# crow.net
KiCad netlist of a schematic drawn in EAGLE
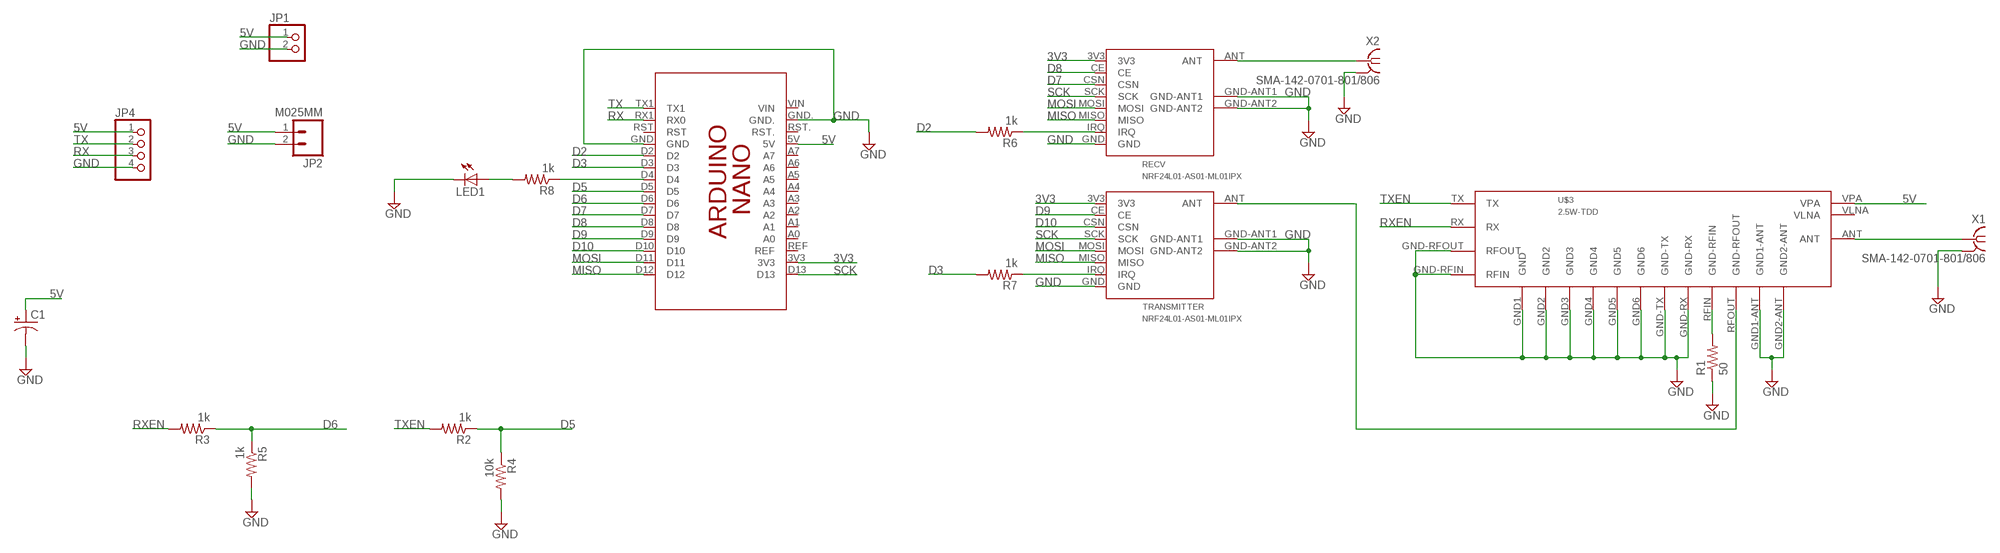
[diagram p0: schematic, sheet 1]

(export (version "E")
  (design (tool "Eeschema 10.0.6"))
  (components
    (comp (ref "C1")
      (value "CPOL-USUD-5X5,8")
      (footprint "eagle-import:UD-5X5,8_NICHICON")
      (libsource (lib "eagle-import") (part "CPOL-USUD-5X5,8"))
    )
    (comp (ref "JP1")
      (value "PINHD-1X2")
      (footprint "eagle-import:1X02")
      (libsource (lib "eagle-import") (part "PINHD-1X2"))
    )
    (comp (ref "JP2")
      (value "M025MM")
      (footprint "eagle-import:SCREWTERMINAL-5MM-2")
      (libsource (lib "eagle-import") (part "M025MM"))
    )
    (comp (ref "JP4")
      (value "PINHD-1X4")
      (footprint "eagle-import:1X04")
      (libsource (lib "eagle-import") (part "PINHD-1X4"))
    )
    (comp (ref "LED1")
      (value "LEDSML0805")
      (footprint "eagle-import:SML0805")
      (libsource (lib "eagle-import") (part "LEDSML0805"))
    )
    (comp (ref "PCB1")
      (value "ARDUINO_NANO_EXT")
      (footprint "eagle-import:ARDUINO_NANO")
      (libsource (lib "eagle-import") (part "ARDUINO_NANO_EXT"))
    )
    (comp (ref "R1")
      (value "50")
      (footprint "eagle-import:M0805")
      (libsource (lib "eagle-import") (part "R-US_M0805"))
    )
    (comp (ref "R2")
      (value "1k")
      (footprint "eagle-import:M0805")
      (libsource (lib "eagle-import") (part "R-US_M0805"))
    )
    (comp (ref "R3")
      (value "1k")
      (footprint "eagle-import:M0805")
      (libsource (lib "eagle-import") (part "R-US_M0805"))
    )
    (comp (ref "R4")
      (value "10k")
      (footprint "eagle-import:M0805")
      (libsource (lib "eagle-import") (part "R-US_M0805"))
    )
    (comp (ref "R5")
      (value "1k")
      (footprint "eagle-import:M0805")
      (libsource (lib "eagle-import") (part "R-US_M0805"))
    )
    (comp (ref "R6")
      (value "1k")
      (footprint "eagle-import:M0805")
      (libsource (lib "eagle-import") (part "R-US_M0805"))
    )
    (comp (ref "R7")
      (value "1k")
      (footprint "eagle-import:M0805")
      (libsource (lib "eagle-import") (part "R-US_M0805"))
    )
    (comp (ref "R8")
      (value "1k")
      (footprint "eagle-import:M0805")
      (libsource (lib "eagle-import") (part "R-US_M0805"))
    )
    (comp (ref "RECV")
      (value "NRF24L01-AS01-ML01IPX")
      (footprint "eagle-import:AS01-ML01IPX")
      (libsource (lib "eagle-import") (part "NRF24L01-AS01-ML01IPX"))
    )
    (comp (ref "TRANSMITTER")
      (value "NRF24L01-AS01-ML01IPX")
      (footprint "eagle-import:AS01-ML01IPX")
      (libsource (lib "eagle-import") (part "NRF24L01-AS01-ML01IPX"))
    )
    (comp (ref "U$3")
      (value "2.5W-TDD")
      (footprint "eagle-import:2.5W-TDD")
      (libsource (lib "eagle-import") (part "2.5W-TDD"))
    )
    (comp (ref "X1")
      (value "SMA-142-0701-801/806")
      (footprint "eagle-import:J502-ND-142-0701-801_806")
      (fields (field (name "MF") "JOHNSON COMPONENTS") (field (name "MPN") "142-0701-801"))
      (libsource (lib "eagle-import") (part "SMA-142-0701-801/806"))
    )
    (comp (ref "X2")
      (value "SMA-142-0701-801/806")
      (footprint "eagle-import:J502-ND-142-0701-801_806")
      (fields (field (name "MF") "JOHNSON COMPONENTS") (field (name "MPN") "142-0701-801"))
      (libsource (lib "eagle-import") (part "SMA-142-0701-801/806"))
    )
  )
  (nets
    (net (code "1") (name "/3V3") (class "Default")
      (node (ref "PCB1") (pin "3V3") (pinfunction "3V3_3V3") (pintype "bidirectional"))
      (node (ref "RECV") (pin "3V3") (pinfunction "3V3_3V3") (pintype "power_in"))
      (node (ref "TRANSMITTER") (pin "3V3") (pinfunction "3V3_3V3") (pintype "power_in"))
    )
    (net (code "2") (name "/5V") (class "Default")
      (node (ref "C1") (pin "+") (pinfunction "+_+") (pintype "passive"))
      (node (ref "JP1") (pin "1") (pinfunction "1_1") (pintype "passive"))
      (node (ref "JP2") (pin "1") (pinfunction "1_1") (pintype "passive"))
      (node (ref "JP4") (pin "1") (pinfunction "1_1") (pintype "passive"))
      (node (ref "PCB1") (pin "5V") (pinfunction "5V_5V") (pintype "bidirectional"))
      (node (ref "U$3") (pin "VPA") (pinfunction "VPA_VPA") (pintype "power_in"))
    )
    (net (code "3") (name "/D2") (class "Default")
      (node (ref "PCB1") (pin "D2") (pinfunction "D2_D2") (pintype "bidirectional"))
      (node (ref "R6") (pin "2") (pinfunction "2_2") (pintype "passive"))
    )
    (net (code "4") (name "/D3") (class "Default")
      (node (ref "PCB1") (pin "D3") (pinfunction "D3_D3") (pintype "bidirectional"))
      (node (ref "R7") (pin "2") (pinfunction "2_2") (pintype "passive"))
    )
    (net (code "5") (name "/D5") (class "Default")
      (node (ref "PCB1") (pin "D5") (pinfunction "D5_D5") (pintype "bidirectional"))
      (node (ref "R2") (pin "1") (pinfunction "1_1") (pintype "passive"))
      (node (ref "R4") (pin "1") (pinfunction "1_1") (pintype "passive"))
    )
    (net (code "6") (name "/D6") (class "Default")
      (node (ref "PCB1") (pin "D6") (pinfunction "D6_D6") (pintype "bidirectional"))
      (node (ref "R3") (pin "1") (pinfunction "1_1") (pintype "passive"))
      (node (ref "R5") (pin "1") (pinfunction "1_1") (pintype "passive"))
    )
    (net (code "7") (name "/D7") (class "Default")
      (node (ref "PCB1") (pin "D7") (pinfunction "D7_D7") (pintype "bidirectional"))
      (node (ref "RECV") (pin "CSN") (pinfunction "CSN_CSN") (pintype "input"))
    )
    (net (code "8") (name "/D8") (class "Default")
      (node (ref "PCB1") (pin "D8") (pinfunction "D8_D8") (pintype "bidirectional"))
      (node (ref "RECV") (pin "CE") (pinfunction "CE_CE") (pintype "input"))
    )
    (net (code "9") (name "/D9") (class "Default")
      (node (ref "PCB1") (pin "D9") (pinfunction "D9_D9") (pintype "bidirectional"))
      (node (ref "TRANSMITTER") (pin "CE") (pinfunction "CE_CE") (pintype "input"))
    )
    (net (code "10") (name "/D10") (class "Default")
      (node (ref "PCB1") (pin "D10") (pinfunction "D10_D10") (pintype "bidirectional"))
      (node (ref "TRANSMITTER") (pin "CSN") (pinfunction "CSN_CSN") (pintype "input"))
    )
    (net (code "11") (name "/MISO") (class "Default")
      (node (ref "PCB1") (pin "D12") (pinfunction "D12_D12") (pintype "bidirectional"))
      (node (ref "RECV") (pin "MISO") (pinfunction "MISO_MISO") (pintype "output"))
      (node (ref "TRANSMITTER") (pin "MISO") (pinfunction "MISO_MISO") (pintype "output"))
    )
    (net (code "12") (name "/MOSI") (class "Default")
      (node (ref "PCB1") (pin "D11") (pinfunction "D11_D11") (pintype "bidirectional"))
      (node (ref "RECV") (pin "MOSI") (pinfunction "MOSI_MOSI") (pintype "input"))
      (node (ref "TRANSMITTER") (pin "MOSI") (pinfunction "MOSI_MOSI") (pintype "input"))
    )
    (net (code "13") (name "/RX") (class "Default")
      (node (ref "JP4") (pin "3") (pinfunction "3_3") (pintype "passive"))
      (node (ref "PCB1") (pin "RX1") (pinfunction "RX0_RX1") (pintype "bidirectional"))
    )
    (net (code "14") (name "/RXEN") (class "Default")
      (node (ref "R3") (pin "2") (pinfunction "2_2") (pintype "passive"))
      (node (ref "U$3") (pin "RX") (pinfunction "RX_RX") (pintype "bidirectional"))
    )
    (net (code "15") (name "/SCK") (class "Default")
      (node (ref "PCB1") (pin "D13") (pinfunction "D13_D13") (pintype "bidirectional"))
      (node (ref "RECV") (pin "SCK") (pinfunction "SCK_SCK") (pintype "input"))
      (node (ref "TRANSMITTER") (pin "SCK") (pinfunction "SCK_SCK") (pintype "input"))
    )
    (net (code "16") (name "/TX") (class "Default")
      (node (ref "JP4") (pin "2") (pinfunction "2_2") (pintype "passive"))
      (node (ref "PCB1") (pin "TX1") (pinfunction "TX1_TX1") (pintype "bidirectional"))
    )
    (net (code "17") (name "/TXEN") (class "Default")
      (node (ref "R2") (pin "2") (pinfunction "2_2") (pintype "passive"))
      (node (ref "U$3") (pin "TX") (pinfunction "TX_TX") (pintype "bidirectional"))
    )
    (net (code "18") (name "/VLNA") (class "Default")
      (node (ref "U$3") (pin "VLNA") (pinfunction "VLNA_VLNA") (pintype "power_in"))
    )
    (net (code "19") (name "GND") (class "Default")
      (node (ref "C1") (pin "-") (pinfunction "-_-") (pintype "passive"))
      (node (ref "JP1") (pin "2") (pinfunction "2_2") (pintype "passive"))
      (node (ref "JP2") (pin "2") (pinfunction "2_2") (pintype "passive"))
      (node (ref "JP4") (pin "4") (pinfunction "4_4") (pintype "passive"))
      (node (ref "LED1") (pin "C") (pinfunction "C_C") (pintype "passive"))
      (node (ref "PCB1") (pin "GND") (pinfunction "GND_GND") (pintype "bidirectional"))
      (node (ref "PCB1") (pin "GND.") (pinfunction "GND._GND.") (pintype "bidirectional"))
      (node (ref "R1") (pin "1") (pinfunction "1_1") (pintype "passive"))
      (node (ref "R4") (pin "2") (pinfunction "2_2") (pintype "passive"))
      (node (ref "R5") (pin "2") (pinfunction "2_2") (pintype "passive"))
      (node (ref "RECV") (pin "GND") (pinfunction "GND_GND") (pintype "power_in"))
      (node (ref "RECV") (pin "GND-ANT1") (pinfunction "GND-ANT1_GND-ANT1") (pintype "power_in"))
      (node (ref "RECV") (pin "GND-ANT2") (pinfunction "GND-ANT2_GND-ANT2") (pintype "power_in"))
      (node (ref "TRANSMITTER") (pin "GND") (pinfunction "GND_GND") (pintype "power_in"))
      (node (ref "TRANSMITTER") (pin "GND-ANT1") (pinfunction "GND-ANT1_GND-ANT1") (pintype "power_in"))
      (node (ref "TRANSMITTER") (pin "GND-ANT2") (pinfunction "GND-ANT2_GND-ANT2") (pintype "power_in"))
      (node (ref "U$3") (pin "GND-RFIN") (pinfunction "RFIN_GND-RFIN") (pintype "output"))
      (node (ref "U$3") (pin "GND-RFOUT") (pinfunction "RFOUT_GND-RFOUT") (pintype "input"))
      (node (ref "U$3") (pin "GND-RX") (pinfunction "GND-RX_GND-RX") (pintype "power_in"))
      (node (ref "U$3") (pin "GND-TX") (pinfunction "GND-TX_GND-TX") (pintype "power_in"))
      (node (ref "U$3") (pin "GND1") (pinfunction "GND_GND1") (pintype "power_in"))
      (node (ref "U$3") (pin "GND1-ANT") (pinfunction "GND1-ANT_GND1-ANT") (pintype "power_in"))
      (node (ref "U$3") (pin "GND2") (pinfunction "GND2_GND2") (pintype "power_in"))
      (node (ref "U$3") (pin "GND2-ANT") (pinfunction "GND2-ANT_GND2-ANT") (pintype "power_in"))
      (node (ref "U$3") (pin "GND3") (pinfunction "GND3_GND3") (pintype "power_in"))
      (node (ref "U$3") (pin "GND4") (pinfunction "GND4_GND4") (pintype "power_in"))
      (node (ref "U$3") (pin "GND5") (pinfunction "GND5_GND5") (pintype "power_in"))
      (node (ref "U$3") (pin "GND6") (pinfunction "GND6_GND6") (pintype "power_in"))
      (node (ref "X1") (pin "G@1") (pinfunction "2_G@1") (pintype "passive"))
      (node (ref "X1") (pin "G@2") (pinfunction "2_G@2") (pintype "passive"))
      (node (ref "X1") (pin "G@3") (pinfunction "2_G@3") (pintype "passive"))
      (node (ref "X1") (pin "G@4") (pinfunction "2_G@4") (pintype "passive"))
      (node (ref "X2") (pin "G@1") (pinfunction "2_G@1") (pintype "passive"))
      (node (ref "X2") (pin "G@2") (pinfunction "2_G@2") (pintype "passive"))
      (node (ref "X2") (pin "G@3") (pinfunction "2_G@3") (pintype "passive"))
      (node (ref "X2") (pin "G@4") (pinfunction "2_G@4") (pintype "passive"))
    )
    (net (code "20") (name "Net-(LED1-PadA)") (class "Default")
      (node (ref "LED1") (pin "A") (pinfunction "A_A") (pintype "passive"))
      (node (ref "R8") (pin "2") (pinfunction "2_2") (pintype "passive"))
    )
    (net (code "21") (name "Net-(PCB1-PadD4)") (class "Default")
      (node (ref "PCB1") (pin "D4") (pinfunction "D4_D4") (pintype "bidirectional"))
      (node (ref "R8") (pin "1") (pinfunction "1_1") (pintype "passive"))
    )
    (net (code "22") (name "Net-(R6-Pad1)") (class "Default")
      (node (ref "R6") (pin "1") (pinfunction "1_1") (pintype "passive"))
      (node (ref "RECV") (pin "IRQ") (pinfunction "IRQ_IRQ") (pintype "output"))
    )
    (net (code "23") (name "Net-(R7-Pad1)") (class "Default")
      (node (ref "R7") (pin "1") (pinfunction "1_1") (pintype "passive"))
      (node (ref "TRANSMITTER") (pin "IRQ") (pinfunction "IRQ_IRQ") (pintype "output"))
    )
    (net (code "24") (name "Net-(RECV-PadANT)") (class "Default")
      (node (ref "RECV") (pin "ANT") (pinfunction "ANT_ANT") (pintype "output"))
      (node (ref "X2") (pin "1") (pinfunction "1_1") (pintype "passive"))
    )
    (net (code "25") (name "Net-(U$3-GND-RFIN)") (class "Default")
      (node (ref "R1") (pin "2") (pinfunction "2_2") (pintype "passive"))
      (node (ref "U$3") (pin "RFIN") (pinfunction "GND-RFIN_RFIN") (pintype "power_in"))
    )
    (net (code "26") (name "Net-(U$3-GND-RFOUT)") (class "Default")
      (node (ref "TRANSMITTER") (pin "ANT") (pinfunction "ANT_ANT") (pintype "output"))
      (node (ref "U$3") (pin "RFOUT") (pinfunction "GND-RFOUT_RFOUT") (pintype "power_in"))
    )
    (net (code "27") (name "Net-(U$3-PadANT)") (class "Default")
      (node (ref "U$3") (pin "ANT") (pinfunction "ANT_ANT") (pintype "output"))
      (node (ref "X1") (pin "1") (pinfunction "1_1") (pintype "passive"))
    )
    (net (code "28") (name "unconnected-(PCB1-PadA0)") (class "Default")
      (node (ref "PCB1") (pin "A0") (pinfunction "A0_A0") (pintype "bidirectional"))
    )
    (net (code "29") (name "unconnected-(PCB1-PadA1)") (class "Default")
      (node (ref "PCB1") (pin "A1") (pinfunction "A1_A1") (pintype "bidirectional"))
    )
    (net (code "30") (name "unconnected-(PCB1-PadA2)") (class "Default")
      (node (ref "PCB1") (pin "A2") (pinfunction "A2_A2") (pintype "bidirectional"))
    )
    (net (code "31") (name "unconnected-(PCB1-PadA3)") (class "Default")
      (node (ref "PCB1") (pin "A3") (pinfunction "A3_A3") (pintype "bidirectional"))
    )
    (net (code "32") (name "unconnected-(PCB1-PadA4)") (class "Default")
      (node (ref "PCB1") (pin "A4") (pinfunction "A4_A4") (pintype "bidirectional"))
    )
    (net (code "33") (name "unconnected-(PCB1-PadA5)") (class "Default")
      (node (ref "PCB1") (pin "A5") (pinfunction "A5_A5") (pintype "bidirectional"))
    )
    (net (code "34") (name "unconnected-(PCB1-PadA6)") (class "Default")
      (node (ref "PCB1") (pin "A6") (pinfunction "A6_A6") (pintype "bidirectional"))
    )
    (net (code "35") (name "unconnected-(PCB1-PadA7)") (class "Default")
      (node (ref "PCB1") (pin "A7") (pinfunction "A7_A7") (pintype "bidirectional"))
    )
    (net (code "36") (name "unconnected-(PCB1-PadREF)") (class "Default")
      (node (ref "PCB1") (pin "REF") (pinfunction "REF_REF") (pintype "bidirectional"))
    )
    (net (code "37") (name "unconnected-(PCB1-PadRST)") (class "Default")
      (node (ref "PCB1") (pin "RST") (pinfunction "RST_RST") (pintype "bidirectional"))
    )
    (net (code "38") (name "unconnected-(PCB1-PadRST.)") (class "Default")
      (node (ref "PCB1") (pin "RST.") (pinfunction "RST._RST.") (pintype "bidirectional"))
    )
    (net (code "39") (name "unconnected-(PCB1-PadVIN)") (class "Default")
      (node (ref "PCB1") (pin "VIN") (pinfunction "VIN_VIN") (pintype "bidirectional"))
    )
  )
)
